# NB680.net
KiCad netlist of a schematic drawn in Altium Designer
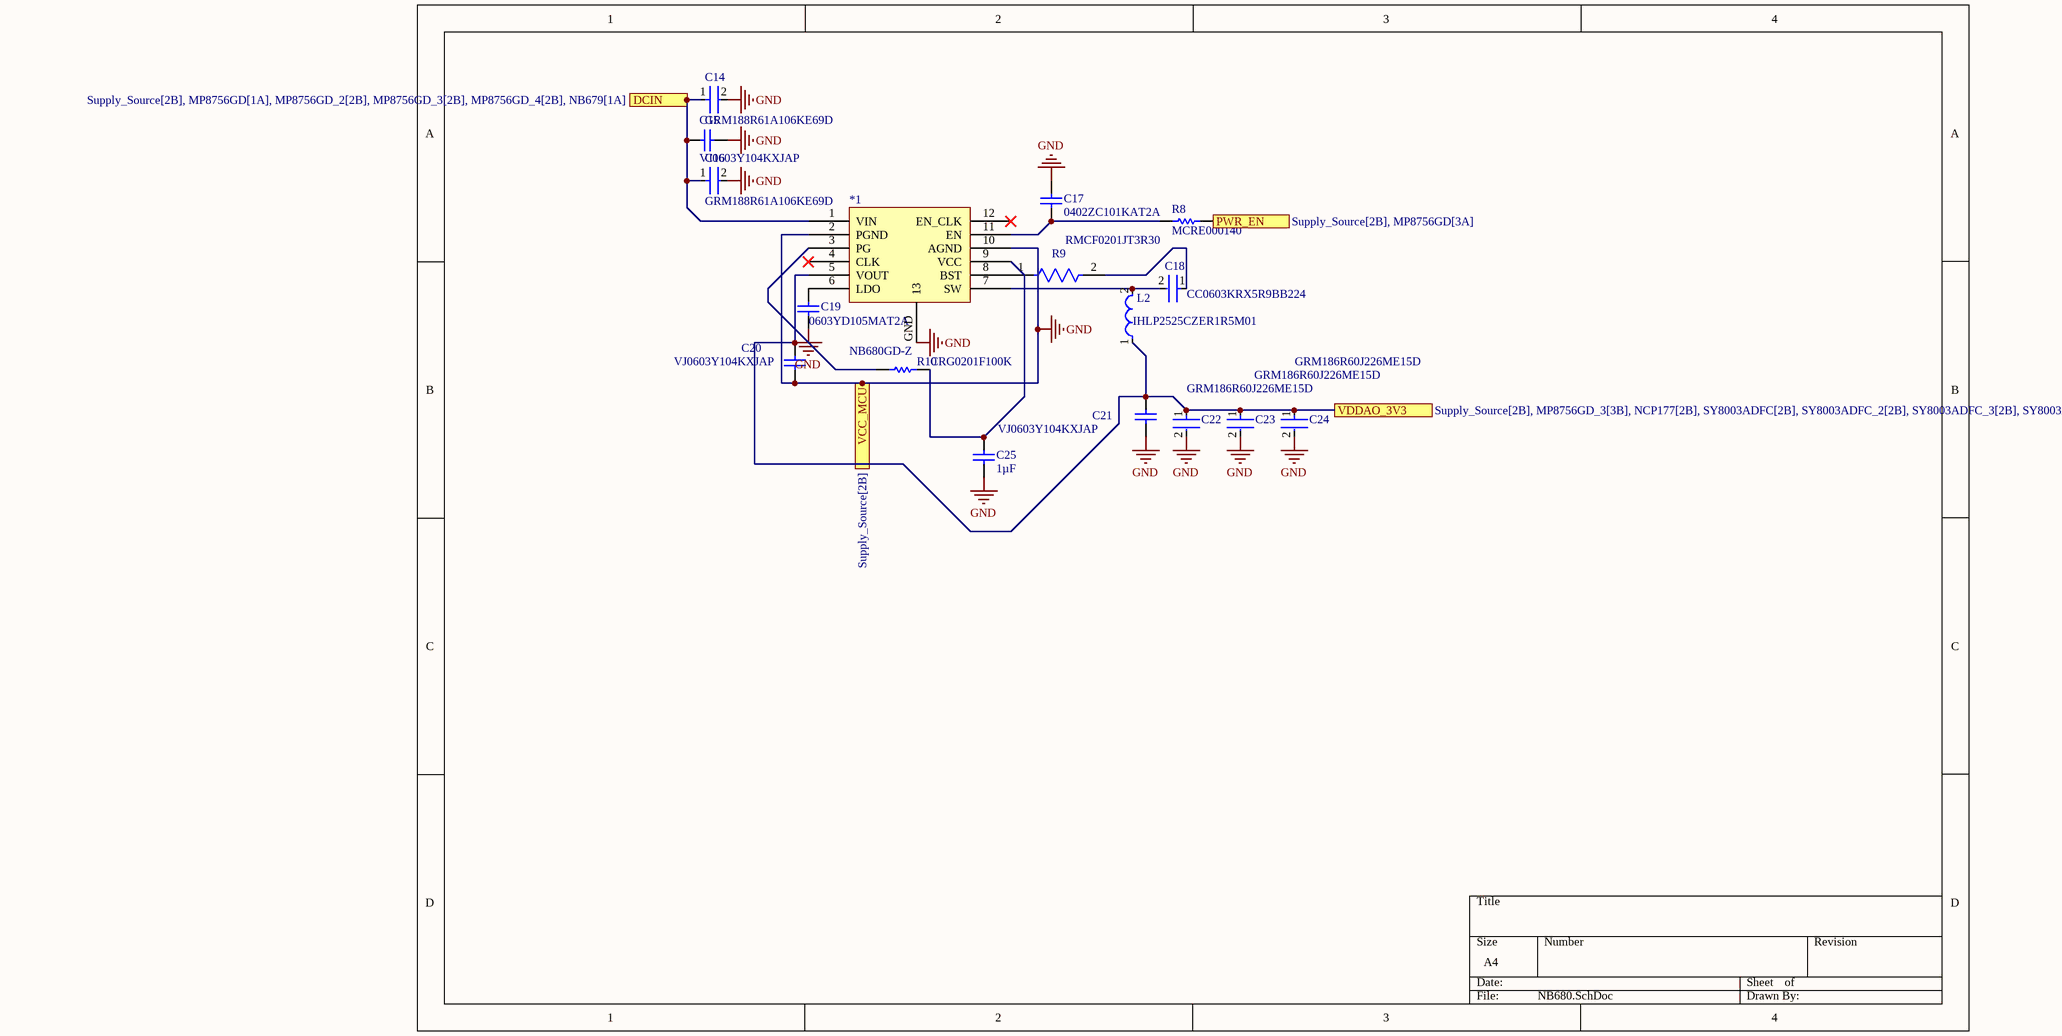
[diagram p0: NB680.SchDoc]

(export (version "E")
  (design (tool "Eeschema 10.0.6"))
  (components
    (comp (ref "*1")
      (value "NB680GD-Z")
      (footprint "NB680GD-Z-Footprint-1")
      (description "Wide Vin 4.8-26V Low Iq High Current Fixed 3.3V-8A Synchronous Buck Converter with 100mA LDO")
      (libsource (lib "MIGUEL ANGEL ALVAREZ GUZMAN") (part "NB680GD-Z-Symbol-1"))
    )
    (comp (ref "C14")
      (value "GRM188R61A106KE69D")
      (footprint "FP-GRM18-0_15-MFG")
      (description "CAP CER 10UF 10V X5R 0603")
      (fields
        (field (name "OCTOPART") "https://octopart.com/grm188r61a106ke69d-murata-22851381")
        (field (name "MANUFACTURER") "Murata")
      )
      (libsource (lib "Altium Content Vault") (part "11868f565c42a9108669ba33697ecf6"))
    )
    (comp (ref "C15")
      (value "VJ0603Y104KXJAP")
      (footprint "CAPC1608X92X38NL15T08")
      (fields (field (name "MANUFACTURER") "Vitramon"))
      (libsource (lib "Altium Content Vault") (part "CAP"))
    )
    (comp (ref "C16")
      (value "GRM188R61A106KE69D")
      (footprint "FP-GRM18-0_15-MFG")
      (description "CAP CER 10UF 10V X5R 0603")
      (fields
        (field (name "OCTOPART") "https://octopart.com/grm188r61a106ke69d-murata-22851381")
        (field (name "MANUFACTURER") "Murata")
      )
      (libsource (lib "Altium Content Vault") (part "11868f565c42a9108669ba33697ecf6"))
    )
    (comp (ref "C17")
      (value "0402ZC101KAT2A")
      (footprint "CAPC1005X56X25NL10T15")
      (fields (field (name "MANUFACTURER") "AVX Interconnect / Elco"))
      (libsource (lib "Altium Content Vault") (part "CAP"))
    )
    (comp (ref "C18")
      (value "CC0603KRX5R9BB224")
      (footprint "FP-CC0603-DA-MFG")
      (description "CC0603 220 nF X5R 10.00% 50 V")
      (fields
        (field (name "TOLERANCE") "0.1")
        (field (name "OCTOPART") "https://octopart.com/cc0603krx5r9bb224-yageo-90326743")
      )
      (libsource (lib "Altium Content Vault") (part "11868f565c42a9108669ba33697ecf6"))
    )
    (comp (ref "C19")
      (value "0603YD105MAT2A")
      (footprint "CAPC1608X90X35NL15T15")
      (fields (field (name "MANUFACTURER") "AVX Interconnect / Elco"))
      (libsource (lib "Altium Content Vault") (part "CAP"))
    )
    (comp (ref "C20")
      (value "VJ0603Y104KXJAP")
      (footprint "CAPC1608X92X38NL15T08")
      (fields (field (name "MANUFACTURER") "Vitramon"))
      (libsource (lib "Altium Content Vault") (part "CAP"))
    )
    (comp (ref "C21")
      (value "VJ0603Y104KXJAP")
      (footprint "CAPC1608X92X38NL15T08")
      (fields (field (name "MANUFACTURER") "Vitramon"))
      (libsource (lib "Altium Content Vault") (part "CAP"))
    )
    (comp (ref "C22")
      (value "GRM186R60J226ME15D")
      (footprint "FP-GRM186-0_2-IPC_B")
      (description "Chip Multilayer Ceramic Capacitors for General Purpose, 0603, 22uF, X5R, 15%, 20%, 6.3V")
      (fields (field (name "TOLERANCE") "20%"))
      (libsource (lib "Altium Content Vault") (part "02cd4be3c70576c341d710602a673aa"))
    )
    (comp (ref "C23")
      (value "GRM186R60J226ME15D")
      (footprint "FP-GRM186-0_2-IPC_B")
      (description "Chip Multilayer Ceramic Capacitors for General Purpose, 0603, 22uF, X5R, 15%, 20%, 6.3V")
      (fields (field (name "TOLERANCE") "20%"))
      (libsource (lib "Altium Content Vault") (part "02cd4be3c70576c341d710602a673aa"))
    )
    (comp (ref "C24")
      (value "GRM186R60J226ME15D")
      (footprint "FP-GRM186-0_2-IPC_B")
      (description "Chip Multilayer Ceramic Capacitors for General Purpose, 0603, 22uF, X5R, 15%, 20%, 6.3V")
      (fields (field (name "TOLERANCE") "20%"))
      (libsource (lib "Altium Content Vault") (part "02cd4be3c70576c341d710602a673aa"))
    )
    (comp (ref "C25")
      (value "1µF")
      (footprint "CAPC1608X90X35LL15T15")
      (description "0603 1 uF 16 V ±20 % Tolerance X5R Surface Mount Multilayer Ceramic Capacitor")
      (fields (field (name "TOLERANCE") "20%") (field (name "Comment") "0603YD105MAT2A"))
      (libsource (lib "MIGUEL ANGEL ALVAREZ GUZMAN") (part "CAP"))
    )
    (comp (ref "L2")
      (value "IHLP2525CZER1R5M01")
      (footprint "FP-IHLP-2525CZ-FP_2_413x3-MFG")
      (description "Commercial Inductors, High Saturation Series 1.5uH 9A 15mΩ 20%")
      (fields (field (name "TOLERANCE") "20%"))
      (libsource (lib "Altium Content Vault") (part "725321dda6339637d4d059423bc1c3c"))
    )
    (comp (ref "R8")
      (value "MCRE000140")
      (footprint "RESC0603X26X15ML03T05")
      (fields (field (name "MANUFACTURER") "Multicomp"))
      (libsource (lib "Altium Content Vault") (part "RES"))
    )
    (comp (ref "R9")
      (value "RMCF0201JT3R30")
      (footprint "FP-RMCF0201-IPC_A")
      (description "3.3Ω ±5% 0.05W 0201 Thick Film Chip Resistor AEC-Q200 compliant")
      (fields (field (name "TOLERANCE") "5%"))
      (libsource (lib "Altium Content Vault") (part "1029c3af85768c4190bb7ad29bc67b5"))
    )
    (comp (ref "R10")
      (value "CRG0201F100K")
      (footprint "RESC0603X26X15LL03T05")
      (fields (field (name "MANUFACTURER") "TE Connectivity / AMP"))
      (libsource (lib "Altium Content Vault") (part "RES"))
    )
  )
  (nets
    (net (code "1") (name "/DCIN") (class "Default")
      (node (ref "*1") (pin "1") (pinfunction "VIN_1") (pintype "passive"))
      (node (ref "C14") (pin "1") (pinfunction "1_1") (pintype "passive"))
      (node (ref "C15") (pin "2") (pinfunction "2_2") (pintype "passive"))
      (node (ref "C16") (pin "1") (pinfunction "1_1") (pintype "passive"))
    )
    (net (code "2") (name "/PWR_EN") (class "Default")
      (node (ref "R8") (pin "2") (pinfunction "2_2") (pintype "passive"))
    )
    (net (code "3") (name "/VDDAO_3V3") (class "Default")
      (node (ref "*1") (pin "5") (pinfunction "VOUT_5") (pintype "passive"))
      (node (ref "C20") (pin "2") (pinfunction "2_2") (pintype "passive"))
      (node (ref "C21") (pin "2") (pinfunction "2_2") (pintype "passive"))
      (node (ref "C22") (pin "1") (pinfunction "1_1") (pintype "passive"))
      (node (ref "C23") (pin "1") (pinfunction "1_1") (pintype "passive"))
      (node (ref "C24") (pin "1") (pinfunction "1_1") (pintype "passive"))
      (node (ref "L2") (pin "1") (pinfunction "1_1") (pintype "passive"))
    )
    (net (code "4") (name "GND") (class "Default")
      (node (ref "*1") (pin "10") (pinfunction "AGND_10") (pintype "passive"))
      (node (ref "*1") (pin "2") (pinfunction "PGND_2") (pintype "passive"))
      (node (ref "*1") (pin "GND") (pinfunction "13_GND") (pintype "passive"))
      (node (ref "C14") (pin "2") (pinfunction "2_2") (pintype "passive"))
      (node (ref "C15") (pin "1") (pinfunction "1_1") (pintype "passive"))
      (node (ref "C16") (pin "2") (pinfunction "2_2") (pintype "passive"))
      (node (ref "C17") (pin "1") (pinfunction "1_1") (pintype "passive"))
      (node (ref "C19") (pin "2") (pinfunction "2_2") (pintype "passive"))
      (node (ref "C20") (pin "1") (pinfunction "1_1") (pintype "passive"))
      (node (ref "C21") (pin "1") (pinfunction "1_1") (pintype "passive"))
      (node (ref "C22") (pin "2") (pinfunction "2_2") (pintype "passive"))
      (node (ref "C23") (pin "2") (pinfunction "2_2") (pintype "passive"))
      (node (ref "C24") (pin "2") (pinfunction "2_2") (pintype "passive"))
      (node (ref "C25") (pin "1") (pinfunction "1_1") (pintype "passive"))
    )
    (net (code "5") (name "Net-(*1-BST)") (class "Default")
      (node (ref "*1") (pin "8") (pinfunction "BST_8") (pintype "passive"))
      (node (ref "R9") (pin "1") (pinfunction "1_1") (pintype "passive"))
    )
    (net (code "6") (name "Net-(*1-EN)") (class "Default")
      (node (ref "*1") (pin "11") (pinfunction "EN_11") (pintype "passive"))
      (node (ref "C17") (pin "2") (pinfunction "2_2") (pintype "passive"))
      (node (ref "R8") (pin "1") (pinfunction "1_1") (pintype "passive"))
    )
    (net (code "7") (name "Net-(*1-LDO)") (class "Default")
      (node (ref "*1") (pin "6") (pinfunction "LDO_6") (pintype "passive"))
      (node (ref "C19") (pin "1") (pinfunction "1_1") (pintype "passive"))
    )
    (net (code "8") (name "Net-(*1-PG)") (class "Default")
      (node (ref "*1") (pin "3") (pinfunction "PG_3") (pintype "passive"))
      (node (ref "R10") (pin "1") (pinfunction "1_1") (pintype "passive"))
    )
    (net (code "9") (name "Net-(*1-SW)") (class "Default")
      (node (ref "*1") (pin "7") (pinfunction "SW_7") (pintype "passive"))
      (node (ref "C18") (pin "2") (pinfunction "2_2") (pintype "passive"))
      (node (ref "L2") (pin "2") (pinfunction "2_2") (pintype "passive"))
    )
    (net (code "10") (name "Net-(*1-VCC)") (class "Default")
      (node (ref "*1") (pin "9") (pinfunction "VCC_9") (pintype "passive"))
      (node (ref "C25") (pin "2") (pinfunction "2_2") (pintype "passive"))
      (node (ref "R10") (pin "2") (pinfunction "2_2") (pintype "passive"))
    )
    (net (code "11") (name "Net-(C18-Pad1)") (class "Default")
      (node (ref "C18") (pin "1") (pinfunction "1_1") (pintype "passive"))
      (node (ref "R9") (pin "2") (pinfunction "2_2") (pintype "passive"))
    )
    (net (code "12") (name "unconnected-(*1-CLK-Pad4)") (class "Default")
      (node (ref "*1") (pin "4") (pinfunction "CLK_4") (pintype "passive+no_connect"))
    )
    (net (code "13") (name "unconnected-(*1-EN_CLK-Pad12)") (class "Default")
      (node (ref "*1") (pin "12") (pinfunction "EN_CLK_12") (pintype "passive+no_connect"))
    )
  )
)
